# AMS1117-3_3_5V_3V3__epro.net
KiCad netlist of a schematic drawn in EasyEDA Pro
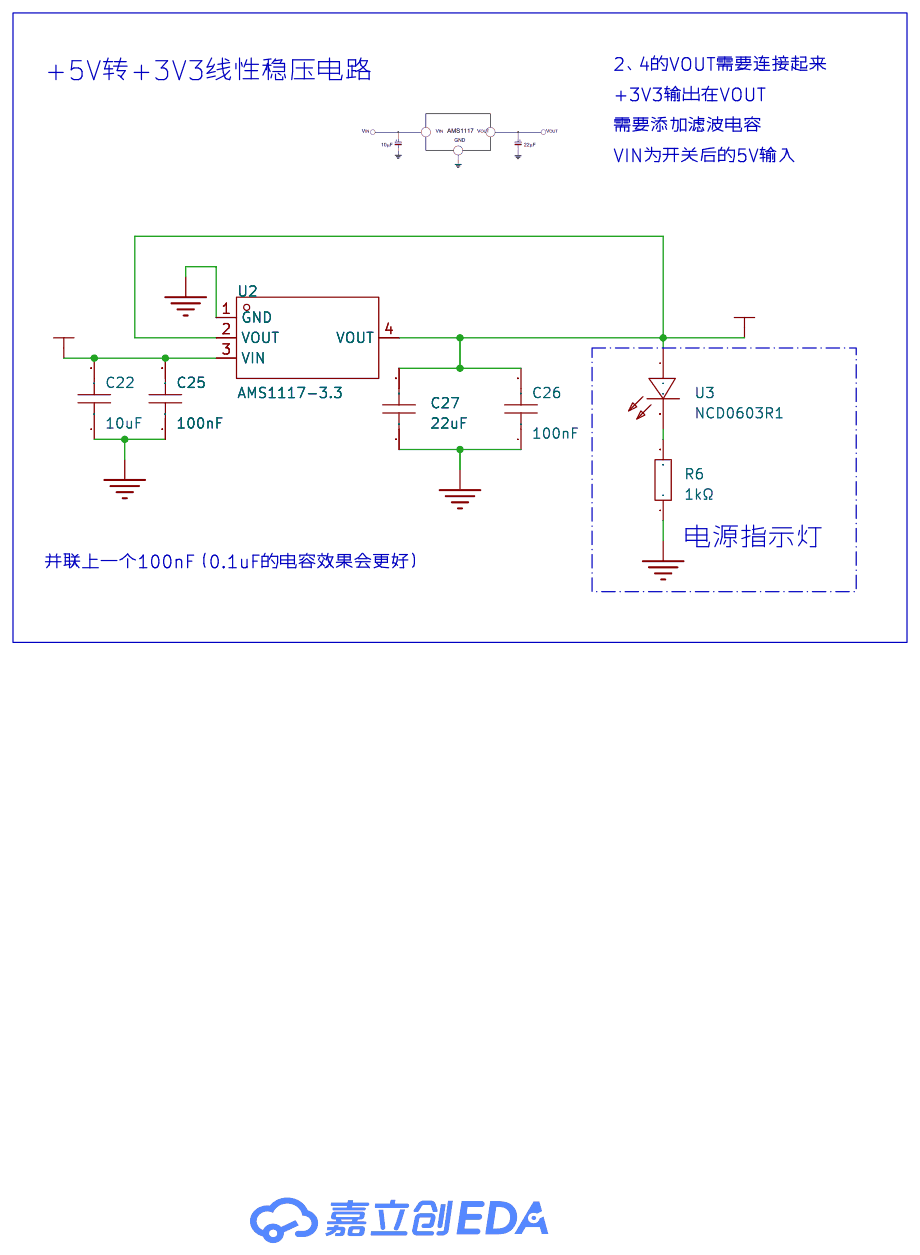
[diagram p0: schematic sheet]

(export (version "E")
  (design (tool "Eeschema 10.0.6"))
  (components
    (comp (ref "C22")
      (value "10uF")
      (footprint "easyedapro:C0603")
      (description "容值:10uF;精度:±10%;额定电压:10V;材质(温度系数):X5R;")
      (fields
        (field (name "Manufacturer Part") "CGA0603X5R106K100JT")
        (field (name "Manufacturer") "HRE(芯声)")
      )
      (libsource (lib "easyedapro") (part "CGA0603X5R106K100JT"))
    )
    (comp (ref "C25")
      (value "100nF")
      (footprint "easyedapro:C0603")
      (description "容值:100nF;精度:±10%;额定电压:50V;材质(温度系数):X7R;")
      (fields
        (field (name "Manufacturer Part") "CGA0603X7R104K500JT")
        (field (name "Manufacturer") "HRE(芯声)")
      )
      (libsource (lib "easyedapro") (part "CGA0603X7R104K500JT"))
    )
    (comp (ref "C26")
      (value "100nF")
      (footprint "easyedapro:C0603")
      (description "容值:100nF;精度:±10%;额定电压:50V;材质(温度系数):X7R;")
      (fields
        (field (name "Manufacturer Part") "CGA0603X7R104K500JT")
        (field (name "Manufacturer") "HRE(芯声)")
      )
      (libsource (lib "easyedapro") (part "CGA0603X7R104K500JT"))
    )
    (comp (ref "C27")
      (value "22uF")
      (footprint "easyedapro:C0805")
      (description "容值:22uF;精度:±20%;额定电压:35V;材质(温度系数):X5R;")
      (fields
        (field (name "Manufacturer Part") "CGA0805X5R226M350MT")
        (field (name "Manufacturer") "HRE(芯声)")
      )
      (libsource (lib "easyedapro") (part "CGA0805X5R226M350MT"))
    )
    (comp (ref "R6")
      (value "1kΩ")
      (footprint "easyedapro:R0603")
      (description "电阻类型:厚膜电阻;阻值:1kΩ;精度:±1%;功率:100mW;最大工作电压:75V;温度系数:±100ppm/°C;")
      (fields
        (field (name "Manufacturer Part") "0603WAF1001T5E")
        (field (name "Manufacturer") "UNI-ROYAL(厚声)")
      )
      (libsource (lib "easyedapro") (part "0603WAF1001T5E"))
    )
    (comp (ref "U2")
      (value "AMS1117-3.3")
      (footprint "easyedapro:SOT-223-3_L6.5-W3.4-P2.30-LS7.0-BR")
      (description "输出类型:固定;最大输入电压:-;输出电压:3.3V;最大输出电流:1A;电源纹波抑制比(PSRR):72dB@(120Hz);输出极性:正极;")
      (fields (field (name "Manufacturer") "AMS"))
      (libsource (lib "easyedapro") (part "AMS1117-3.3"))
    )
    (comp (ref "U3")
      (value "NCD0603R1")
      (footprint "easyedapro:LED0603-R-RD")
      (libsource (lib "easyedapro") (part "NCD0603R1"))
    )
  )
  (nets
    (net (code "1") (name "+3V3") (class "Default")
      (node (ref "C26") (pin "2") (pinfunction "2_2") (pintype "unspecified"))
      (node (ref "C27") (pin "2") (pinfunction "2_2") (pintype "unspecified"))
      (node (ref "U2") (pin "2") (pinfunction "VOUT_2") (pintype "unspecified"))
      (node (ref "U2") (pin "4") (pinfunction "VOUT_4") (pintype "unspecified"))
      (node (ref "U3") (pin "1") (pinfunction "A_1") (pintype "unspecified"))
    )
    (net (code "2") (name "+5V") (class "Default")
      (node (ref "C22") (pin "2") (pinfunction "2_2") (pintype "unspecified"))
      (node (ref "C25") (pin "2") (pinfunction "2_2") (pintype "unspecified"))
      (node (ref "U2") (pin "3") (pinfunction "VIN_3") (pintype "unspecified"))
    )
    (net (code "3") (name "GND") (class "Default")
      (node (ref "C22") (pin "1") (pinfunction "1_1") (pintype "unspecified"))
      (node (ref "C25") (pin "1") (pinfunction "1_1") (pintype "unspecified"))
      (node (ref "C26") (pin "1") (pinfunction "1_1") (pintype "unspecified"))
      (node (ref "C27") (pin "1") (pinfunction "1_1") (pintype "unspecified"))
      (node (ref "R6") (pin "1") (pinfunction "1_1") (pintype "input"))
      (node (ref "U2") (pin "1") (pinfunction "GND_1") (pintype "unspecified"))
    )
    (net (code "4") (name "Net-(U3-K)") (class "Default")
      (node (ref "R6") (pin "2") (pinfunction "2_2") (pintype "input"))
      (node (ref "U3") (pin "2") (pinfunction "K_2") (pintype "unspecified"))
    )
  )
)
